# 6_Audio_Full_bridge.net
KiCad netlist of a schematic drawn in Altium Designer
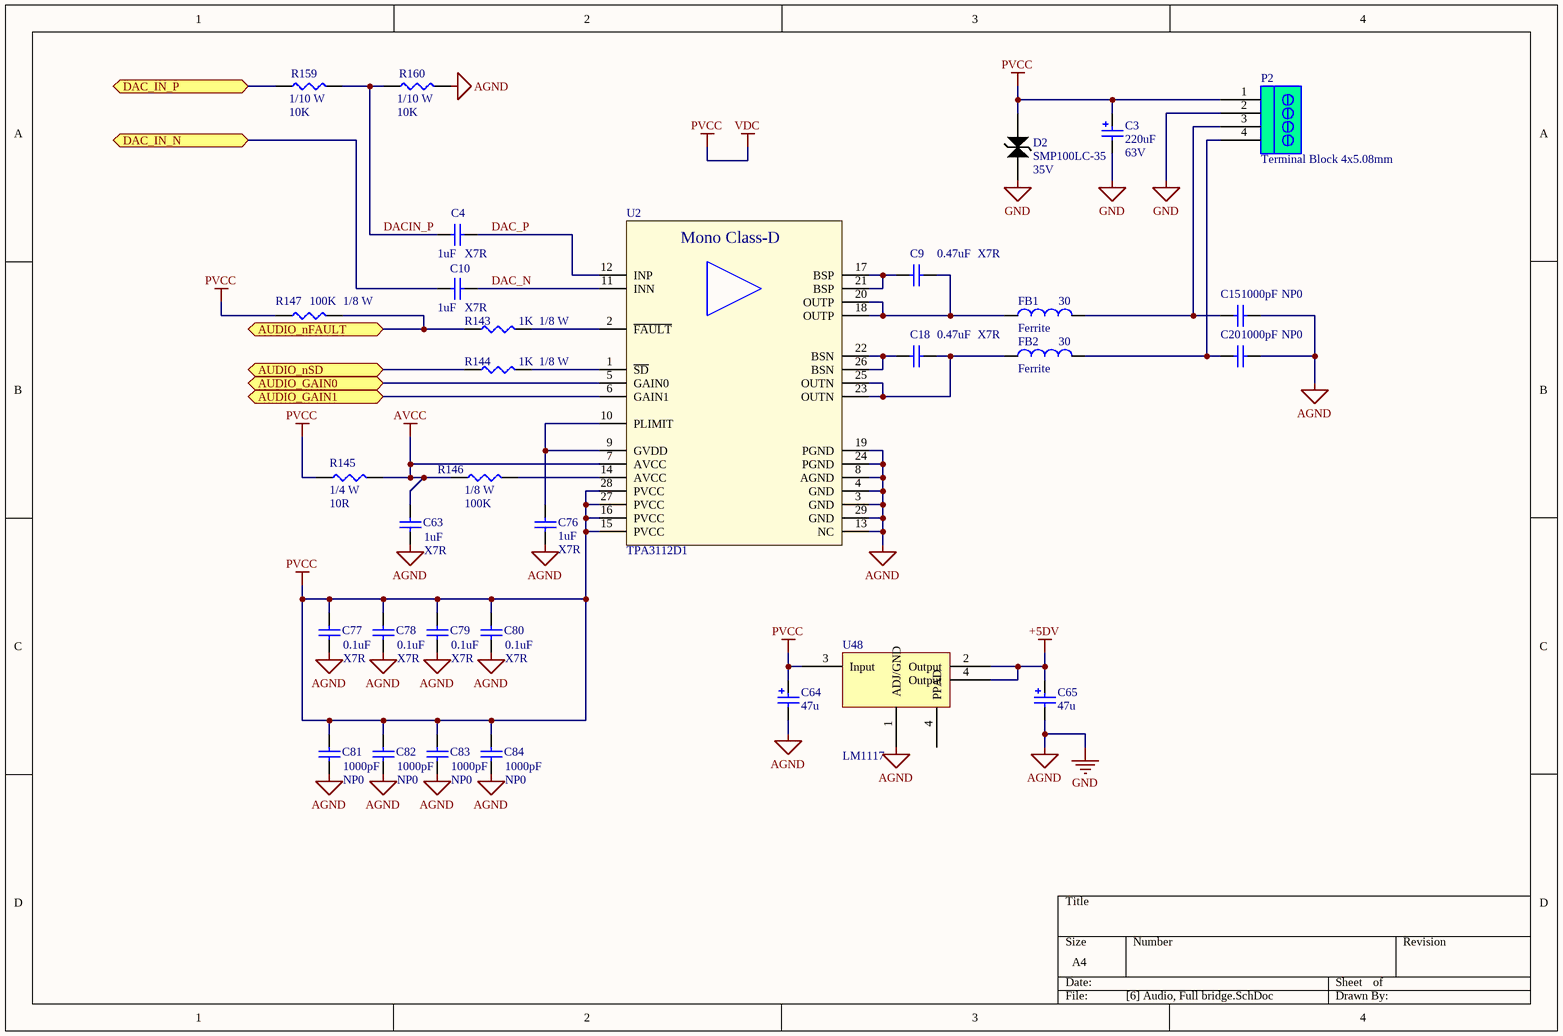
[diagram p0: [6] Audio, Full bridge.SchDoc]

(export (version "E")
  (design (tool "Eeschema 10.0.6"))
  (components
    (comp (ref "C3")
      (value "220uF")
      (footprint "CAPPR5-10x17_1")
      (description "Polarized Capacitor (Radial) Very low impedance")
      (fields
        (field (name "VOLTAGE") "63V")
        (field (name "MANUFACTURER PART NUMBER") "SC063M0220A5S-1019")
        (field (name "Comment") "Cap Pol 100/47")
      )
      (libsource (lib "Common Devices") (part "Cap Pol 100/47"))
    )
    (comp (ref "C4")
      (value "1uF")
      (footprint "CAP0805")
      (description "Surface-mount ceramic multilayer capacitor")
      (fields (field (name "VOLTAGE") "16V") (field (name "TOLERANCE") "5%") (field (name "TYPE") "X7R"))
      (libsource (lib "Capacitors") (part "CAP0805 1uF X7R"))
    )
    (comp (ref "C9")
      (value "0.47uF")
      (footprint "CAP0603")
      (description "Surface-mount ceramic multilayer capacitor")
      (fields (field (name "VOLTAGE") "100V") (field (name "TOLERANCE") "10%") (field (name "TYPE") "X7R"))
      (libsource (lib "Capacitors") (part "ChipCap 0.47uF X7R"))
    )
    (comp (ref "C10")
      (value "1uF")
      (footprint "CAP0805")
      (description "Surface-mount ceramic multilayer capacitor")
      (fields (field (name "VOLTAGE") "16V") (field (name "TOLERANCE") "5%") (field (name "TYPE") "X7R"))
      (libsource (lib "Capacitors") (part "CAP0805 1uF X7R"))
    )
    (comp (ref "C15")
      (value "1000pF")
      (footprint "CAP0805")
      (description "Surface-mount ceramic multilayer capacitor")
      (fields (field (name "VOLTAGE") "50V") (field (name "TOLERANCE") "5%") (field (name "TYPE") "NP0"))
      (libsource (lib "Capacitors") (part "CAP0805 1000pF NP0"))
    )
    (comp (ref "C18")
      (value "0.47uF")
      (footprint "CAP0603")
      (description "Surface-mount ceramic multilayer capacitor")
      (fields (field (name "VOLTAGE") "100V") (field (name "TOLERANCE") "10%") (field (name "TYPE") "X7R"))
      (libsource (lib "Capacitors") (part "ChipCap 0.47uF X7R"))
    )
    (comp (ref "C20")
      (value "1000pF")
      (footprint "CAP0805")
      (description "Surface-mount ceramic multilayer capacitor")
      (fields (field (name "VOLTAGE") "50V") (field (name "TOLERANCE") "5%") (field (name "TYPE") "NP0"))
      (libsource (lib "Capacitors") (part "CAP0805 1000pF NP0"))
    )
    (comp (ref "C63")
      (value "1uF")
      (footprint "CAP0805")
      (description "Surface-mount ceramic multilayer capacitor")
      (fields (field (name "VOLTAGE") "16V") (field (name "TOLERANCE") "5%") (field (name "TYPE") "X7R"))
      (libsource (lib "Capacitors") (part "CAP0805 1uF X7R"))
    )
    (comp (ref "C64")
      (value "47u")
      (footprint "CAPC7343")
      (description "Polarized Capacitor (Radial)")
      (fields (field (name "Comment") "Cap Pol SMD"))
      (libsource (lib "Common Devices") (part "Cap Pol Chip"))
    )
    (comp (ref "C65")
      (value "47u")
      (footprint "CAPC7343")
      (description "Polarized Capacitor (Radial)")
      (fields (field (name "Comment") "Cap Pol SMD"))
      (libsource (lib "Common Devices") (part "Cap Pol Chip"))
    )
    (comp (ref "C76")
      (value "1uF")
      (footprint "CAP0805")
      (description "Surface-mount ceramic multilayer capacitor")
      (fields (field (name "VOLTAGE") "16V") (field (name "TOLERANCE") "5%") (field (name "TYPE") "X7R"))
      (libsource (lib "Capacitors") (part "CAP0805 1uF X7R"))
    )
    (comp (ref "C77")
      (value "0.1uF")
      (footprint "CAP0805")
      (description "Surface-mount ceramic multilayer capacitor")
      (fields (field (name "VOLTAGE") "50V") (field (name "TOLERANCE") "5%") (field (name "TYPE") "X7R"))
      (libsource (lib "Capacitors") (part "CAP0805 0.1uF X7R"))
    )
    (comp (ref "C78")
      (value "0.1uF")
      (footprint "CAP0805")
      (description "Surface-mount ceramic multilayer capacitor")
      (fields (field (name "VOLTAGE") "50V") (field (name "TOLERANCE") "5%") (field (name "TYPE") "X7R"))
      (libsource (lib "Capacitors") (part "CAP0805 0.1uF X7R"))
    )
    (comp (ref "C79")
      (value "0.1uF")
      (footprint "CAP0805")
      (description "Surface-mount ceramic multilayer capacitor")
      (fields (field (name "VOLTAGE") "50V") (field (name "TOLERANCE") "5%") (field (name "TYPE") "X7R"))
      (libsource (lib "Capacitors") (part "CAP0805 0.1uF X7R"))
    )
    (comp (ref "C80")
      (value "0.1uF")
      (footprint "CAP0805")
      (description "Surface-mount ceramic multilayer capacitor")
      (fields (field (name "VOLTAGE") "50V") (field (name "TOLERANCE") "5%") (field (name "TYPE") "X7R"))
      (libsource (lib "Capacitors") (part "CAP0805 0.1uF X7R"))
    )
    (comp (ref "C81")
      (value "1000pF")
      (footprint "CAP0603")
      (description "Surface-mount ceramic multilayer capacitor")
      (fields (field (name "VOLTAGE") "16V") (field (name "TOLERANCE") "10%") (field (name "TYPE") "NP0"))
      (libsource (lib "Capacitors") (part "ChipCap 1000 X7R"))
    )
    (comp (ref "C82")
      (value "1000pF")
      (footprint "CAP0603")
      (description "Surface-mount ceramic multilayer capacitor")
      (fields (field (name "VOLTAGE") "16V") (field (name "TOLERANCE") "10%") (field (name "TYPE") "NP0"))
      (libsource (lib "Capacitors") (part "ChipCap 1000 X7R"))
    )
    (comp (ref "C83")
      (value "1000pF")
      (footprint "CAP0603")
      (description "Surface-mount ceramic multilayer capacitor")
      (fields (field (name "VOLTAGE") "16V") (field (name "TOLERANCE") "10%") (field (name "TYPE") "NP0"))
      (libsource (lib "Capacitors") (part "ChipCap 1000 X7R"))
    )
    (comp (ref "C84")
      (value "1000pF")
      (footprint "CAP0603")
      (description "Surface-mount ceramic multilayer capacitor")
      (fields (field (name "VOLTAGE") "16V") (field (name "TOLERANCE") "10%") (field (name "TYPE") "NP0"))
      (libsource (lib "Capacitors") (part "ChipCap 1000 X7R"))
    )
    (comp (ref "D2")
      (value "SMP100LC-35")
      (footprint "SMB1")
      (description "Transient Voltage Suppressor 600W bi-directional")
      (fields (field (name "VOLTAGE") "35V"))
      (libsource (lib "Protection") (part "SMP100LC-35"))
    )
    (comp (ref "FB1")
      (value "Ferrite")
      (footprint "RES0805")
      (fields
        (field (name "ALTIUM_VALUE") "30")
        (field (name "MANUFACTURER") "BOURNS")
        (field (name "MANUFACTURER PART NUMBER") "MH2029-300Y")
      )
      (libsource (lib "Common Devices") (part "Ferrite Bead"))
    )
    (comp (ref "FB2")
      (value "Ferrite")
      (footprint "RES0805")
      (fields
        (field (name "ALTIUM_VALUE") "30")
        (field (name "MANUFACTURER") "BOURNS")
        (field (name "MANUFACTURER PART NUMBER") "MH2029-300Y")
      )
      (libsource (lib "Common Devices") (part "Ferrite Bead"))
    )
    (comp (ref "P2")
      (value "Terminal Block 4x5.08mm")
      (footprint "Socket 4x5.08")
      (description "Terminal Block Socket Right Angle 4x5.08mm 2-Wall")
      (libsource (lib "IndustrialConnectors") (part "Socket_4x5.08_RA_2Wall"))
    )
    (comp (ref "R143")
      (value "1K")
      (footprint "RES0805")
      (description "Think Film Chip resistor")
      (fields
        (field (name "TOLERANCE") "1%")
        (field (name "MANUFACTURER PART NUMBER") "RC0805FR-071KL")
        (field (name "RATING") "1/8 W")
      )
      (libsource (lib "Resistors") (part "RES0805 1K 1%"))
    )
    (comp (ref "R144")
      (value "1K")
      (footprint "RES0805")
      (description "Think Film Chip resistor")
      (fields
        (field (name "TOLERANCE") "1%")
        (field (name "MANUFACTURER PART NUMBER") "RC0805FR-071KL")
        (field (name "RATING") "1/8 W")
      )
      (libsource (lib "Resistors") (part "RES0805 1K 1%"))
    )
    (comp (ref "R145")
      (value "10R")
      (footprint "RES1206")
      (description "Think Film Chip resistor")
      (fields
        (field (name "TOLERANCE") "1%")
        (field (name "MANUFACTURER PART NUMBER") "RC1206FR-0710RL")
        (field (name "RATING") "1/4 W")
      )
      (libsource (lib "Resistors") (part "RES1206 10R 1%"))
    )
    (comp (ref "R146")
      (value "100K")
      (footprint "RES0805")
      (description "Think Film Chip resistor")
      (fields
        (field (name "TOLERANCE") "1%")
        (field (name "MANUFACTURER PART NUMBER") "RC0805FR-07100KL")
        (field (name "RATING") "1/8 W")
      )
      (libsource (lib "Resistors") (part "RES0805 100K 1%"))
    )
    (comp (ref "R147")
      (value "100K")
      (footprint "RES0805")
      (description "Think Film Chip resistor")
      (fields
        (field (name "TOLERANCE") "1%")
        (field (name "MANUFACTURER PART NUMBER") "RC0805FR-07100RL")
        (field (name "RATING") "1/8 W")
      )
      (libsource (lib "Resistors") (part "RES0805 100R 1%"))
    )
    (comp (ref "R159")
      (value "10K")
      (footprint "RES0603")
      (description "Think Film Chip resistor")
      (fields
        (field (name "TOLERANCE") "1%")
        (field (name "MANUFACTURER PART NUMBER") "RC0603FR-0710KL (YAG)")
        (field (name "RATING") "1/10 W")
      )
      (libsource (lib "Resistors") (part "RES0603 10K 1%"))
    )
    (comp (ref "R160")
      (value "10K")
      (footprint "RES0603")
      (description "Think Film Chip resistor")
      (fields
        (field (name "TOLERANCE") "1%")
        (field (name "MANUFACTURER PART NUMBER") "RC0603FR-0710KL (YAG)")
        (field (name "RATING") "1/10 W")
      )
      (libsource (lib "Resistors") (part "RES0603 10K 1%"))
    )
    (comp (ref "U2")
      (value "TPA3112D1")
      (footprint "TSSOP-28")
      (description "25-W filter-free mono class-D audio power amplifier with speaker guard")
      (fields (field (name "MANUFACTURER PART NUMBER") "TPA3112D1PWP") (field (name "POWER") "25W"))
      (libsource (lib "TI Audio Amplifier class-D") (part "TPA3112D1"))
    )
    (comp (ref "U48")
      (value "LM1117")
      (footprint "SOT223-4M")
      (description "Power Mgt Voltage Regulator")
      (libsource (lib "TI Step Motor Driver") (part "LM1117"))
    )
  )
  (nets
    (net (code "1") (name "+5DV") (class "Default")
      (node (ref "C65") (pin "1") (pinfunction "1_1") (pintype "passive"))
      (node (ref "U48") (pin "2") (pinfunction "Output_2") (pintype "power_in"))
      (node (ref "U48") (pin "4") (pinfunction "Output_4") (pintype "power_in"))
    )
    (net (code "2") (name "/AUDIO_GAIN0") (class "Default")
      (node (ref "U2") (pin "5") (pinfunction "GAIN0_5") (pintype "passive"))
    )
    (net (code "3") (name "/AUDIO_GAIN1") (class "Default")
      (node (ref "U2") (pin "6") (pinfunction "GAIN1_6") (pintype "passive"))
    )
    (net (code "4") (name "/AUDIO_nFAULT") (class "Default")
      (node (ref "R143") (pin "1") (pintype "passive"))
      (node (ref "R147") (pin "2") (pintype "passive"))
    )
    (net (code "5") (name "/AUDIO_nSD") (class "Default") (node (ref "R144") (pin "1") (pintype "passive")))
    (net (code "6") (name "/DACIN_P") (class "Default")
      (node (ref "C4") (pin "1") (pinfunction "1_1") (pintype "passive"))
      (node (ref "R159") (pin "2") (pintype "passive"))
      (node (ref "R160") (pin "1") (pintype "passive"))
    )
    (net (code "7") (name "/DAC_IN_N") (class "Default")
      (node (ref "C10") (pin "1") (pinfunction "1_1") (pintype "passive"))
    )
    (net (code "8") (name "/DAC_IN_P") (class "Default") (node (ref "R159") (pin "1") (pintype "passive")))
    (net (code "9") (name "/DAC_N") (class "Default")
      (node (ref "C10") (pin "2") (pinfunction "2_2") (pintype "passive"))
      (node (ref "U2") (pin "11") (pinfunction "INN_11") (pintype "passive"))
    )
    (net (code "10") (name "/DAC_P") (class "Default")
      (node (ref "C4") (pin "2") (pinfunction "2_2") (pintype "passive"))
      (node (ref "U2") (pin "12") (pinfunction "INP_12") (pintype "passive"))
    )
    (net (code "11") (name "AGND") (class "Default")
      (node (ref "C15") (pin "2") (pinfunction "2_2") (pintype "passive"))
      (node (ref "C20") (pin "2") (pinfunction "2_2") (pintype "passive"))
      (node (ref "C3") (pin "2") (pinfunction "2_2") (pintype "passive"))
      (node (ref "C63") (pin "1") (pinfunction "1_1") (pintype "passive"))
      (node (ref "C64") (pin "2") (pinfunction "2_2") (pintype "passive"))
      (node (ref "C65") (pin "2") (pinfunction "2_2") (pintype "passive"))
      (node (ref "C76") (pin "2") (pinfunction "2_2") (pintype "passive"))
      (node (ref "C77") (pin "1") (pinfunction "1_1") (pintype "passive"))
      (node (ref "C78") (pin "1") (pinfunction "1_1") (pintype "passive"))
      (node (ref "C79") (pin "1") (pinfunction "1_1") (pintype "passive"))
      (node (ref "C80") (pin "1") (pinfunction "1_1") (pintype "passive"))
      (node (ref "C81") (pin "1") (pinfunction "1_1") (pintype "passive"))
      (node (ref "C82") (pin "1") (pinfunction "1_1") (pintype "passive"))
      (node (ref "C83") (pin "1") (pinfunction "1_1") (pintype "passive"))
      (node (ref "C84") (pin "1") (pinfunction "1_1") (pintype "passive"))
      (node (ref "D2") (pin "1") (pinfunction "1_1") (pintype "passive"))
      (node (ref "P2") (pin "2") (pintype "passive"))
      (node (ref "R160") (pin "2") (pintype "passive"))
      (node (ref "U2") (pin "13") (pinfunction "NC_13") (pintype "passive"))
      (node (ref "U2") (pin "19") (pinfunction "PGND_19") (pintype "passive"))
      (node (ref "U2") (pin "24") (pinfunction "PGND_24") (pintype "passive"))
      (node (ref "U2") (pin "29") (pinfunction "GND_29") (pintype "passive"))
      (node (ref "U2") (pin "3") (pinfunction "GND_3") (pintype "passive"))
      (node (ref "U2") (pin "4") (pinfunction "GND_4") (pintype "passive"))
      (node (ref "U2") (pin "8") (pinfunction "AGND_8") (pintype "passive"))
      (node (ref "U48") (pin "1") (pinfunction "ADJ/GND_1") (pintype "power_in"))
    )
    (net (code "12") (name "AVCC") (class "Default")
      (node (ref "C63") (pin "2") (pinfunction "2_2") (pintype "passive"))
      (node (ref "R145") (pin "2") (pintype "passive"))
      (node (ref "R146") (pin "1") (pintype "passive"))
      (node (ref "U2") (pin "7") (pinfunction "AVCC_7") (pintype "passive"))
    )
    (net (code "13") (name "Net-(C9-Pad1)") (class "Default")
      (node (ref "C9") (pin "1") (pinfunction "1_1") (pintype "passive"))
      (node (ref "U2") (pin "17") (pinfunction "BSP_17") (pintype "passive"))
      (node (ref "U2") (pin "21") (pinfunction "BSP_21") (pintype "passive"))
    )
    (net (code "14") (name "Net-(C9-Pad2)") (class "Default")
      (node (ref "C9") (pin "2") (pinfunction "2_2") (pintype "passive"))
      (node (ref "FB1") (pin "1") (pinfunction "1_1") (pintype "passive"))
      (node (ref "U2") (pin "18") (pinfunction "OUTP_18") (pintype "passive"))
      (node (ref "U2") (pin "20") (pinfunction "OUTP_20") (pintype "passive"))
    )
    (net (code "15") (name "Net-(C15-Pad1)") (class "Default")
      (node (ref "C15") (pin "1") (pinfunction "1_1") (pintype "passive"))
      (node (ref "FB1") (pin "2") (pinfunction "2_2") (pintype "passive"))
      (node (ref "P2") (pin "3") (pintype "passive"))
    )
    (net (code "16") (name "Net-(C18-Pad1)") (class "Default")
      (node (ref "C18") (pin "1") (pinfunction "1_1") (pintype "passive"))
      (node (ref "U2") (pin "22") (pinfunction "BSN_22") (pintype "passive"))
      (node (ref "U2") (pin "26") (pinfunction "BSN_26") (pintype "passive"))
    )
    (net (code "17") (name "Net-(C18-Pad2)") (class "Default")
      (node (ref "C18") (pin "2") (pinfunction "2_2") (pintype "passive"))
      (node (ref "FB2") (pin "1") (pinfunction "1_1") (pintype "passive"))
      (node (ref "U2") (pin "23") (pinfunction "OUTN_23") (pintype "passive"))
      (node (ref "U2") (pin "25") (pinfunction "OUTN_25") (pintype "passive"))
    )
    (net (code "18") (name "Net-(C20-Pad1)") (class "Default")
      (node (ref "C20") (pin "1") (pinfunction "1_1") (pintype "passive"))
      (node (ref "FB2") (pin "2") (pinfunction "2_2") (pintype "passive"))
      (node (ref "P2") (pin "4") (pintype "passive"))
    )
    (net (code "19") (name "Net-(R146-Pad2)") (class "Default")
      (node (ref "R146") (pin "2") (pintype "passive"))
      (node (ref "U2") (pin "14") (pinfunction "AVCC_14") (pintype "passive"))
    )
    (net (code "20") (name "Net-(U2-GVDD)") (class "Default")
      (node (ref "C76") (pin "1") (pinfunction "1_1") (pintype "passive"))
      (node (ref "U2") (pin "10") (pinfunction "PLIMIT_10") (pintype "passive"))
      (node (ref "U2") (pin "9") (pinfunction "GVDD_9") (pintype "passive"))
    )
    (net (code "21") (name "Net-(U2-~{FAULT})") (class "Default")
      (node (ref "R143") (pin "2") (pintype "passive"))
      (node (ref "U2") (pin "2") (pinfunction "~{FAULT}_2") (pintype "passive"))
    )
    (net (code "22") (name "Net-(U2-~{SD})") (class "Default")
      (node (ref "R144") (pin "2") (pintype "passive"))
      (node (ref "U2") (pin "1") (pinfunction "~{SD}_1") (pintype "passive"))
    )
    (net (code "23") (name "PVCC") (class "Default")
      (node (ref "C3") (pin "1") (pinfunction "1_1") (pintype "passive"))
      (node (ref "C64") (pin "1") (pinfunction "1_1") (pintype "passive"))
      (node (ref "C77") (pin "2") (pinfunction "2_2") (pintype "passive"))
      (node (ref "C78") (pin "2") (pinfunction "2_2") (pintype "passive"))
      (node (ref "C79") (pin "2") (pinfunction "2_2") (pintype "passive"))
      (node (ref "C80") (pin "2") (pinfunction "2_2") (pintype "passive"))
      (node (ref "C81") (pin "2") (pinfunction "2_2") (pintype "passive"))
      (node (ref "C82") (pin "2") (pinfunction "2_2") (pintype "passive"))
      (node (ref "C83") (pin "2") (pinfunction "2_2") (pintype "passive"))
      (node (ref "C84") (pin "2") (pinfunction "2_2") (pintype "passive"))
      (node (ref "D2") (pin "2") (pinfunction "2_2") (pintype "passive"))
      (node (ref "P2") (pin "1") (pintype "passive"))
      (node (ref "R145") (pin "1") (pintype "passive"))
      (node (ref "R147") (pin "1") (pintype "passive"))
      (node (ref "U2") (pin "15") (pinfunction "PVCC_15") (pintype "passive"))
      (node (ref "U2") (pin "16") (pinfunction "PVCC_16") (pintype "passive"))
      (node (ref "U2") (pin "27") (pinfunction "PVCC_27") (pintype "passive"))
      (node (ref "U2") (pin "28") (pinfunction "PVCC_28") (pintype "passive"))
      (node (ref "U48") (pin "3") (pinfunction "Input_3") (pintype "power_in"))
    )
    (net (code "24") (name "unconnected-(U48-PPAD-Pad4)") (class "Default")
      (node (ref "U48") (pin "4") (pinfunction "PPAD_4") (pintype "passive"))
    )
  )
)
